# switch.net
KiCad netlist of a schematic drawn in EAGLE
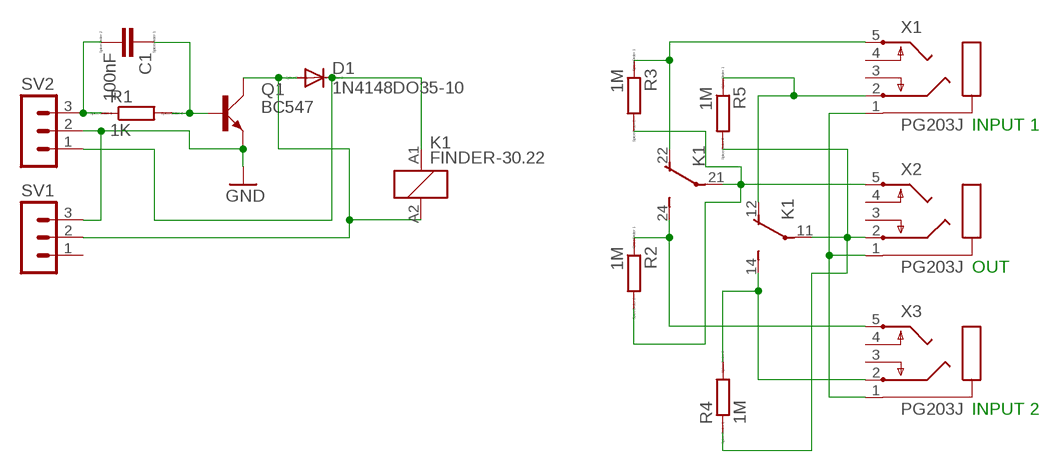
[diagram p0: schematic, sheet 1]

(export (version "E")
  (design (tool "Eeschema 10.0.6"))
  (components
    (comp (ref "C1")
      (value "100nF")
      (footprint "eagle-import:C025-025X050")
      (libsource (lib "eagle-import") (part "C-EU025-025X050"))
    )
    (comp (ref "D1")
      (value "1N4148DO35-10")
      (footprint "eagle-import:DO35-10")
      (libsource (lib "eagle-import") (part "1N4148DO35-10"))
    )
    (comp (ref "K1")
      (value "FINDER-30.22")
      (footprint "eagle-import:FINDER-30.22")
      (libsource (lib "eagle-import") (part "FINDER-30.22"))
    )
    (comp (ref "Q1")
      (value "BC547")
      (footprint "eagle-import:SOT54A")
      (libsource (lib "eagle-import") (part "BC547"))
    )
    (comp (ref "R1")
      (value "1K")
      (footprint "eagle-import:0207_10")
      (libsource (lib "eagle-import") (part "R-EU_0207_10"))
    )
    (comp (ref "R2")
      (value "1M")
      (footprint "eagle-import:0207_10")
      (libsource (lib "eagle-import") (part "R-EU_0207_10"))
    )
    (comp (ref "R3")
      (value "1M")
      (footprint "eagle-import:0207_10")
      (libsource (lib "eagle-import") (part "R-EU_0207_10"))
    )
    (comp (ref "R4")
      (value "1M")
      (footprint "eagle-import:0207_10")
      (libsource (lib "eagle-import") (part "R-EU_0207_10"))
    )
    (comp (ref "R5")
      (value "1M")
      (footprint "eagle-import:0207_10")
      (libsource (lib "eagle-import") (part "R-EU_0207_10"))
    )
    (comp (ref "SV1")
      (value "MA03-1")
      (footprint "eagle-import:MA03-1")
      (libsource (lib "eagle-import") (part "MA03-1"))
    )
    (comp (ref "SV2")
      (value "MA03-1")
      (footprint "eagle-import:MA03-1")
      (libsource (lib "eagle-import") (part "MA03-1"))
    )
    (comp (ref "X1")
      (value "PG203J")
      (footprint "eagle-import:PG203J")
      (libsource (lib "eagle-import") (part "PG203J"))
    )
    (comp (ref "X2")
      (value "PG203J")
      (footprint "eagle-import:PG203J")
      (libsource (lib "eagle-import") (part "PG203J"))
    )
    (comp (ref "X3")
      (value "PG203J")
      (footprint "eagle-import:PG203J")
      (libsource (lib "eagle-import") (part "PG203J"))
    )
  )
  (nets
    (net (code "1") (name "GND") (class "Default")
      (node (ref "Q1") (pin "E") (pinfunction "E_E") (pintype "passive"))
      (node (ref "SV1") (pin "3") (pinfunction "3_3") (pintype "passive"))
      (node (ref "SV2") (pin "2") (pinfunction "2_2") (pintype "passive"))
    )
    (net (code "2") (name "Net-(C1-Pad1)") (class "Default")
      (node (ref "C1") (pin "1") (pinfunction "1_1") (pintype "passive"))
      (node (ref "Q1") (pin "B") (pinfunction "B_B") (pintype "passive"))
      (node (ref "R1") (pin "2") (pinfunction "2_2") (pintype "passive"))
    )
    (net (code "3") (name "Net-(C1-Pad2)") (class "Default")
      (node (ref "C1") (pin "2") (pinfunction "2_2") (pintype "passive"))
      (node (ref "R1") (pin "1") (pinfunction "1_1") (pintype "passive"))
      (node (ref "SV2") (pin "3") (pinfunction "3_3") (pintype "passive"))
    )
    (net (code "4") (name "Net-(K1A-O)") (class "Default")
      (node (ref "K1") (pin "12") (pinfunction "O_12") (pintype "passive"))
      (node (ref "R5") (pin "1") (pinfunction "1_1") (pintype "passive"))
      (node (ref "X1") (pin "2") (pinfunction "2_2") (pintype "passive"))
    )
    (net (code "5") (name "Net-(K1A-P)") (class "Default")
      (node (ref "K1") (pin "11") (pinfunction "P_11") (pintype "passive"))
      (node (ref "R4") (pin "1") (pinfunction "1_1") (pintype "passive"))
      (node (ref "R5") (pin "2") (pinfunction "2_2") (pintype "passive"))
      (node (ref "X2") (pin "2") (pinfunction "2_2") (pintype "passive"))
    )
    (net (code "6") (name "Net-(K1A-S)") (class "Default")
      (node (ref "K1") (pin "14") (pinfunction "S_14") (pintype "passive"))
      (node (ref "R4") (pin "2") (pinfunction "2_2") (pintype "passive"))
      (node (ref "X3") (pin "2") (pinfunction "2_2") (pintype "passive"))
    )
    (net (code "7") (name "Net-(K1B-O)") (class "Default")
      (node (ref "K1") (pin "22") (pinfunction "O_22") (pintype "passive"))
      (node (ref "R3") (pin "1") (pinfunction "1_1") (pintype "passive"))
      (node (ref "X1") (pin "5") (pinfunction "5_5") (pintype "passive"))
    )
    (net (code "8") (name "Net-(K1B-P)") (class "Default")
      (node (ref "K1") (pin "21") (pinfunction "P_21") (pintype "passive"))
      (node (ref "R2") (pin "2") (pinfunction "2_2") (pintype "passive"))
      (node (ref "R3") (pin "2") (pinfunction "2_2") (pintype "passive"))
      (node (ref "X2") (pin "5") (pinfunction "5_5") (pintype "passive"))
    )
    (net (code "9") (name "Net-(K1B-S)") (class "Default")
      (node (ref "K1") (pin "24") (pinfunction "S_24") (pintype "passive"))
      (node (ref "R2") (pin "1") (pinfunction "1_1") (pintype "passive"))
      (node (ref "X3") (pin "5") (pinfunction "5_5") (pintype "passive"))
    )
    (net (code "10") (name "Net-(K1C-1)") (class "Default")
      (node (ref "D1") (pin "C") (pinfunction "C_C") (pintype "passive"))
      (node (ref "K1") (pin "A1") (pinfunction "1_A1") (pintype "passive"))
      (node (ref "SV2") (pin "1") (pinfunction "1_1") (pintype "passive"))
    )
    (net (code "11") (name "Net-(K1C-2)") (class "Default")
      (node (ref "D1") (pin "A") (pinfunction "A_A") (pintype "passive"))
      (node (ref "K1") (pin "A2") (pinfunction "2_A2") (pintype "passive"))
      (node (ref "Q1") (pin "C") (pinfunction "C_C") (pintype "passive"))
      (node (ref "SV1") (pin "2") (pinfunction "2_2") (pintype "passive"))
    )
    (net (code "12") (name "Net-(X1-Pad1)") (class "Default")
      (node (ref "X1") (pin "1") (pinfunction "1_1") (pintype "passive"))
      (node (ref "X2") (pin "1") (pinfunction "1_1") (pintype "passive"))
      (node (ref "X3") (pin "1") (pinfunction "1_1") (pintype "passive"))
    )
    (net (code "13") (name "unconnected-(SV1-Pad1)") (class "Default")
      (node (ref "SV1") (pin "1") (pinfunction "1_1") (pintype "passive"))
    )
    (net (code "14") (name "unconnected-(X1-Pad3)") (class "Default")
      (node (ref "X1") (pin "3") (pinfunction "3_3") (pintype "passive"))
    )
    (net (code "15") (name "unconnected-(X1-Pad4)") (class "Default")
      (node (ref "X1") (pin "4") (pinfunction "4_4") (pintype "passive"))
    )
    (net (code "16") (name "unconnected-(X2-Pad3)") (class "Default")
      (node (ref "X2") (pin "3") (pinfunction "3_3") (pintype "passive"))
    )
    (net (code "17") (name "unconnected-(X2-Pad4)") (class "Default")
      (node (ref "X2") (pin "4") (pinfunction "4_4") (pintype "passive"))
    )
    (net (code "18") (name "unconnected-(X3-Pad3)") (class "Default")
      (node (ref "X3") (pin "3") (pinfunction "3_3") (pintype "passive"))
    )
    (net (code "19") (name "unconnected-(X3-Pad4)") (class "Default")
      (node (ref "X3") (pin "4") (pinfunction "4_4") (pintype "passive"))
    )
  )
)
